# microcontroller.net
KiCad netlist of a schematic drawn in EAGLE
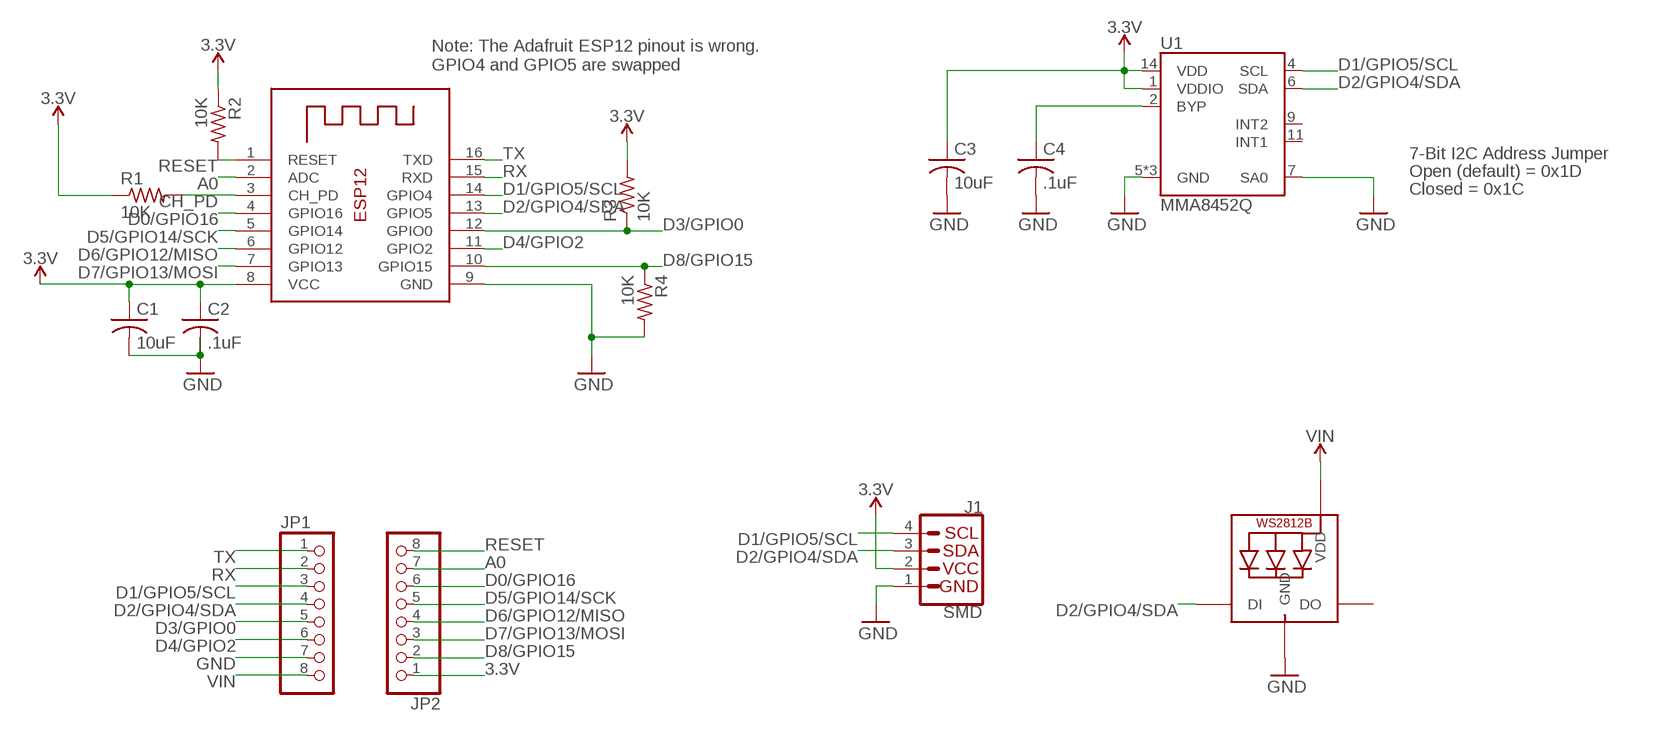
[diagram p0: schematic, sheet 1]

(export (version "E")
  (design (tool "Eeschema 10.0.6"))
  (components
    (comp (ref "C1")
      (value "10uF")
      (footprint "eagle-import:C0805")
      (fields (field (name "MPN") "LMK212BJ106KG-T"))
      (libsource (lib "eagle-import") (part "C-USC0805"))
    )
    (comp (ref "C2")
      (value ".1uF")
      (footprint "eagle-import:C0805")
      (fields (field (name "MPN") "C0805C104M3RACTU"))
      (libsource (lib "eagle-import") (part "C-USC0805"))
    )
    (comp (ref "C3")
      (value "10uF")
      (footprint "eagle-import:C0805")
      (fields (field (name "MPN") "LMK212BJ106KG-T"))
      (libsource (lib "eagle-import") (part "C-USC0805"))
    )
    (comp (ref "C4")
      (value ".1uF")
      (footprint "eagle-import:C0805")
      (fields (field (name "MPN") "C0805C104M3RACTU"))
      (libsource (lib "eagle-import") (part "C-USC0805"))
    )
    (comp (ref "J1")
      (value "SMD")
      (footprint "eagle-import:1X04_1MM_RA")
      (fields (field (name "MPN") "PRT-14417"))
      (libsource (lib "eagle-import") (part "I2C_STANDARDJS-1MM"))
    )
    (comp (ref "JP1")
      (value "PINHD-1X8CLEANBIG")
      (footprint "eagle-import:1X08-CLEANBIG")
      (fields (field (name "MPN") "8Fx1L-254mm"))
      (libsource (lib "eagle-import") (part "PINHD-1X8CLEANBIG"))
    )
    (comp (ref "JP2")
      (value "PINHD-1X8CLEANBIG")
      (footprint "eagle-import:1X08-CLEANBIG")
      (fields (field (name "MPN") "8Fx1L-254mm"))
      (libsource (lib "eagle-import") (part "PINHD-1X8CLEANBIG"))
    )
    (comp (ref "LED1")
      (value "WS2812B5050")
      (footprint "eagle-import:WS2812B")
      (fields (field (name "MPN") "1655"))
      (libsource (lib "eagle-import") (part "WS2812B5050"))
    )
    (comp (ref "R1")
      (value "10K")
      (footprint "eagle-import:R0805")
      (fields (field (name "MPN") "CRCW080510K0FKEAC"))
      (libsource (lib "eagle-import") (part "R-US_R0805"))
    )
    (comp (ref "R2")
      (value "10K")
      (footprint "eagle-import:R0805")
      (fields (field (name "MPN") "CRCW080510K0FKEAC"))
      (libsource (lib "eagle-import") (part "R-US_R0805"))
    )
    (comp (ref "R3")
      (value "10K")
      (footprint "eagle-import:R0805")
      (fields (field (name "MPN") "CRCW080510K0FKEAC"))
      (libsource (lib "eagle-import") (part "R-US_R0805"))
    )
    (comp (ref "R4")
      (value "10K")
      (footprint "eagle-import:R0805")
      (fields (field (name "MPN") "CRCW080510K0FKEAC"))
      (libsource (lib "eagle-import") (part "R-US_R0805"))
    )
    (comp (ref "U1")
      (value "MMA8452Q")
      (footprint "eagle-import:QFN-16_0.5MM")
      (fields (field (name "MPN") "MMA8452QR1"))
      (libsource (lib "eagle-import") (part "MMA8452Q"))
    )
    (comp (ref "X1")
      (value "ESP-12")
      (footprint "eagle-import:ESP-12")
      (fields (field (name "MPN") "ESP12"))
      (libsource (lib "eagle-import") (part "ESP-12"))
    )
  )
  (nets
    (net (code "1") (name "/A0") (class "Default")
      (node (ref "JP2") (pin "7") (pinfunction "7_7") (pintype "passive"))
      (node (ref "X1") (pin "2") (pinfunction "ADC_2") (pintype "passive"))
    )
    (net (code "2") (name "/CH_PD") (class "Default")
      (node (ref "R1") (pin "2") (pinfunction "2_2") (pintype "passive"))
      (node (ref "X1") (pin "3") (pinfunction "CH_PD_3") (pintype "input"))
    )
    (net (code "3") (name "/D0{slash}GPIO16") (class "Default")
      (node (ref "JP2") (pin "6") (pinfunction "6_6") (pintype "passive"))
      (node (ref "X1") (pin "4") (pinfunction "GPIO16_4") (pintype "bidirectional"))
    )
    (net (code "4") (name "/D1{slash}GPIO5{slash}SCL") (class "Default")
      (node (ref "J1") (pin "4") (pinfunction "SCL_4") (pintype "passive"))
      (node (ref "JP1") (pin "3") (pinfunction "3_3") (pintype "passive"))
      (node (ref "U1") (pin "4") (pinfunction "SCL_4") (pintype "bidirectional"))
      (node (ref "X1") (pin "14") (pinfunction "GPIO4_14") (pintype "bidirectional"))
    )
    (net (code "5") (name "/D2{slash}GPIO4{slash}SDA") (class "Default")
      (node (ref "J1") (pin "3") (pinfunction "SDA_3") (pintype "passive"))
      (node (ref "JP1") (pin "4") (pinfunction "4_4") (pintype "passive"))
      (node (ref "LED1") (pin "4-DIN") (pinfunction "DI_4-DIN") (pintype "input"))
      (node (ref "U1") (pin "6") (pinfunction "SDA_6") (pintype "bidirectional"))
      (node (ref "X1") (pin "13") (pinfunction "GPIO5_13") (pintype "bidirectional"))
    )
    (net (code "6") (name "/D3{slash}GPIO0") (class "Default")
      (node (ref "JP1") (pin "5") (pinfunction "5_5") (pintype "passive"))
      (node (ref "R3") (pin "1") (pinfunction "1_1") (pintype "passive"))
      (node (ref "X1") (pin "12") (pinfunction "GPIO0_12") (pintype "bidirectional"))
    )
    (net (code "7") (name "/D4{slash}GPIO2") (class "Default")
      (node (ref "JP1") (pin "6") (pinfunction "6_6") (pintype "passive"))
      (node (ref "X1") (pin "11") (pinfunction "GPIO2_11") (pintype "bidirectional"))
    )
    (net (code "8") (name "/D5{slash}GPIO14{slash}SCK") (class "Default")
      (node (ref "JP2") (pin "5") (pinfunction "5_5") (pintype "passive"))
      (node (ref "X1") (pin "5") (pinfunction "GPIO14_5") (pintype "bidirectional"))
    )
    (net (code "9") (name "/D6{slash}GPIO12{slash}MISO") (class "Default")
      (node (ref "JP2") (pin "4") (pinfunction "4_4") (pintype "passive"))
      (node (ref "X1") (pin "6") (pinfunction "GPIO12_6") (pintype "bidirectional"))
    )
    (net (code "10") (name "/D7{slash}GPIO13{slash}MOSI") (class "Default")
      (node (ref "JP2") (pin "3") (pinfunction "3_3") (pintype "passive"))
      (node (ref "X1") (pin "7") (pinfunction "GPIO13_7") (pintype "bidirectional"))
    )
    (net (code "11") (name "/D8{slash}GPIO15") (class "Default")
      (node (ref "JP2") (pin "2") (pinfunction "2_2") (pintype "passive"))
      (node (ref "R4") (pin "1") (pinfunction "1_1") (pintype "passive"))
      (node (ref "X1") (pin "10") (pinfunction "GPIO15_10") (pintype "bidirectional"))
    )
    (net (code "12") (name "/RESET") (class "Default")
      (node (ref "JP2") (pin "8") (pinfunction "8_8") (pintype "passive"))
      (node (ref "R2") (pin "2") (pinfunction "2_2") (pintype "passive"))
      (node (ref "X1") (pin "1") (pinfunction "RESET_1") (pintype "input"))
    )
    (net (code "13") (name "/RX") (class "Default")
      (node (ref "JP1") (pin "2") (pinfunction "2_2") (pintype "passive"))
      (node (ref "X1") (pin "15") (pinfunction "RXD_15") (pintype "input"))
    )
    (net (code "14") (name "/TX") (class "Default")
      (node (ref "JP1") (pin "1") (pinfunction "1_1") (pintype "passive"))
      (node (ref "X1") (pin "16") (pinfunction "TXD_16") (pintype "output"))
    )
    (net (code "15") (name "3.3V") (class "Default")
      (node (ref "C1") (pin "1") (pinfunction "1_1") (pintype "passive"))
      (node (ref "C2") (pin "1") (pinfunction "1_1") (pintype "passive"))
      (node (ref "C3") (pin "1") (pinfunction "1_1") (pintype "passive"))
      (node (ref "J1") (pin "2") (pinfunction "VCC_2") (pintype "power_in"))
      (node (ref "JP2") (pin "1") (pinfunction "1_1") (pintype "passive"))
      (node (ref "R1") (pin "1") (pinfunction "1_1") (pintype "passive"))
      (node (ref "R2") (pin "1") (pinfunction "1_1") (pintype "passive"))
      (node (ref "R3") (pin "2") (pinfunction "2_2") (pintype "passive"))
      (node (ref "U1") (pin "1") (pinfunction "VDDIO_1") (pintype "bidirectional"))
      (node (ref "U1") (pin "14") (pinfunction "VDD_14") (pintype "bidirectional"))
      (node (ref "X1") (pin "8") (pinfunction "VCC_8") (pintype "power_in"))
    )
    (net (code "16") (name "GND") (class "Default")
      (node (ref "C1") (pin "2") (pinfunction "2_2") (pintype "passive"))
      (node (ref "C2") (pin "2") (pinfunction "2_2") (pintype "passive"))
      (node (ref "C3") (pin "2") (pinfunction "2_2") (pintype "passive"))
      (node (ref "C4") (pin "2") (pinfunction "2_2") (pintype "passive"))
      (node (ref "J1") (pin "1") (pinfunction "GND_1") (pintype "power_in"))
      (node (ref "JP1") (pin "7") (pinfunction "7_7") (pintype "passive"))
      (node (ref "LED1") (pin "3-GND") (pinfunction "GND_3-GND") (pintype "power_in"))
      (node (ref "R4") (pin "2") (pinfunction "2_2") (pintype "passive"))
      (node (ref "U1") (pin "10") (pinfunction "GND_10") (pintype "bidirectional"))
      (node (ref "U1") (pin "12") (pinfunction "GND_12") (pintype "bidirectional"))
      (node (ref "U1") (pin "5") (pinfunction "GND_5") (pintype "bidirectional"))
      (node (ref "U1") (pin "7") (pinfunction "SA0_7") (pintype "bidirectional"))
      (node (ref "X1") (pin "9") (pinfunction "GND_9") (pintype "power_in"))
    )
    (net (code "17") (name "Net-(U1-BYP)") (class "Default")
      (node (ref "C4") (pin "1") (pinfunction "1_1") (pintype "passive"))
      (node (ref "U1") (pin "2") (pinfunction "BYP_2") (pintype "bidirectional"))
    )
    (net (code "18") (name "VIN") (class "Default")
      (node (ref "JP1") (pin "8") (pinfunction "8_8") (pintype "passive"))
      (node (ref "LED1") (pin "1-VDD") (pinfunction "VDD_1-VDD") (pintype "power_in"))
    )
    (net (code "19") (name "unconnected-(LED1-DO-Pad2-DOUT)") (class "Default")
      (node (ref "LED1") (pin "2-DOUT") (pinfunction "DO_2-DOUT") (pintype "output"))
    )
    (net (code "20") (name "unconnected-(U1-INT1-Pad11)") (class "Default")
      (node (ref "U1") (pin "11") (pinfunction "INT1_11") (pintype "bidirectional"))
    )
    (net (code "21") (name "unconnected-(U1-INT2-Pad9)") (class "Default")
      (node (ref "U1") (pin "9") (pinfunction "INT2_9") (pintype "bidirectional"))
    )
  )
)
